# led_cube.net
KiCad netlist of a schematic drawn in EAGLE
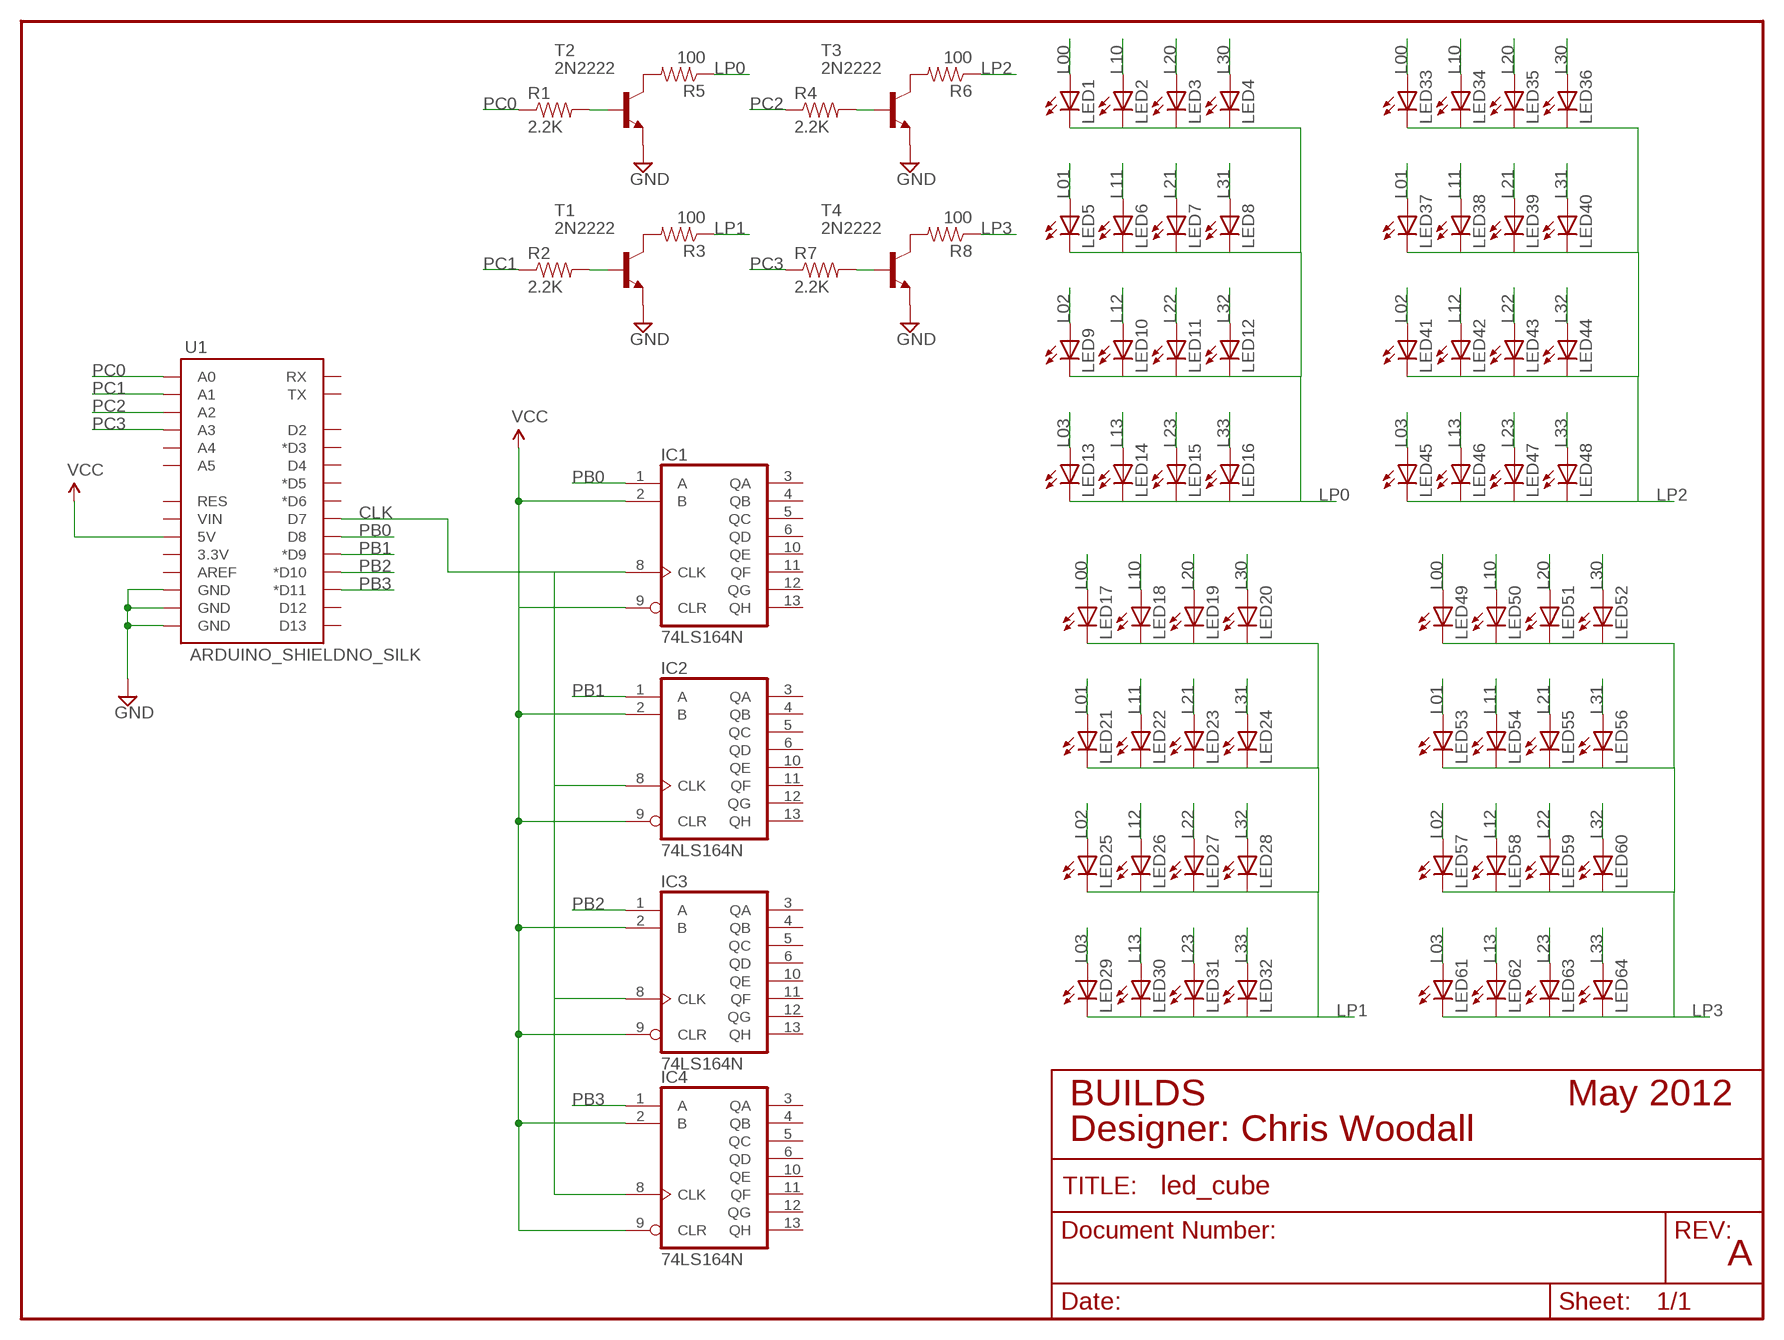
[diagram p0: schematic, sheet 1]

(export (version "E")
  (design (tool "Eeschema 10.0.6"))
  (components
    (comp (ref "IC1")
      (value "74LS164N")
      (footprint "eagle-import:DIL14")
      (libsource (lib "eagle-import") (part "74164NLS"))
    )
    (comp (ref "IC2")
      (value "74LS164N")
      (footprint "eagle-import:DIL14")
      (libsource (lib "eagle-import") (part "74164NLS"))
    )
    (comp (ref "IC3")
      (value "74LS164N")
      (footprint "eagle-import:DIL14")
      (libsource (lib "eagle-import") (part "74164NLS"))
    )
    (comp (ref "IC4")
      (value "74LS164N")
      (footprint "eagle-import:DIL14")
      (libsource (lib "eagle-import") (part "74164NLS"))
    )
    (comp (ref "LED1")
      (value "LED")
      (footprint "eagle-import:SMARTLED-TTW")
      (libsource (lib "eagle-import") (part "LED"))
    )
    (comp (ref "LED2")
      (value "LED")
      (footprint "eagle-import:SMARTLED-TTW")
      (libsource (lib "eagle-import") (part "LED"))
    )
    (comp (ref "LED3")
      (value "LED")
      (footprint "eagle-import:SMARTLED-TTW")
      (libsource (lib "eagle-import") (part "LED"))
    )
    (comp (ref "LED4")
      (value "LED")
      (footprint "eagle-import:SMARTLED-TTW")
      (libsource (lib "eagle-import") (part "LED"))
    )
    (comp (ref "LED5")
      (value "LED")
      (footprint "eagle-import:SMARTLED-TTW")
      (libsource (lib "eagle-import") (part "LED"))
    )
    (comp (ref "LED6")
      (value "LED")
      (footprint "eagle-import:SMARTLED-TTW")
      (libsource (lib "eagle-import") (part "LED"))
    )
    (comp (ref "LED7")
      (value "LED")
      (footprint "eagle-import:SMARTLED-TTW")
      (libsource (lib "eagle-import") (part "LED"))
    )
    (comp (ref "LED8")
      (value "LED")
      (footprint "eagle-import:SMARTLED-TTW")
      (libsource (lib "eagle-import") (part "LED"))
    )
    (comp (ref "LED9")
      (value "LED")
      (footprint "eagle-import:SMARTLED-TTW")
      (libsource (lib "eagle-import") (part "LED"))
    )
    (comp (ref "LED10")
      (value "LED")
      (footprint "eagle-import:SMARTLED-TTW")
      (libsource (lib "eagle-import") (part "LED"))
    )
    (comp (ref "LED11")
      (value "LED")
      (footprint "eagle-import:SMARTLED-TTW")
      (libsource (lib "eagle-import") (part "LED"))
    )
    (comp (ref "LED12")
      (value "LED")
      (footprint "eagle-import:SMARTLED-TTW")
      (libsource (lib "eagle-import") (part "LED"))
    )
    (comp (ref "LED13")
      (value "LED")
      (footprint "eagle-import:SMARTLED-TTW")
      (libsource (lib "eagle-import") (part "LED"))
    )
    (comp (ref "LED14")
      (value "LED")
      (footprint "eagle-import:SMARTLED-TTW")
      (libsource (lib "eagle-import") (part "LED"))
    )
    (comp (ref "LED15")
      (value "LED")
      (footprint "eagle-import:SMARTLED-TTW")
      (libsource (lib "eagle-import") (part "LED"))
    )
    (comp (ref "LED16")
      (value "LED")
      (footprint "eagle-import:SMARTLED-TTW")
      (libsource (lib "eagle-import") (part "LED"))
    )
    (comp (ref "LED17")
      (value "LED")
      (footprint "eagle-import:SMARTLED-TTW")
      (libsource (lib "eagle-import") (part "LED"))
    )
    (comp (ref "LED18")
      (value "LED")
      (footprint "eagle-import:SMARTLED-TTW")
      (libsource (lib "eagle-import") (part "LED"))
    )
    (comp (ref "LED19")
      (value "LED")
      (footprint "eagle-import:SMARTLED-TTW")
      (libsource (lib "eagle-import") (part "LED"))
    )
    (comp (ref "LED20")
      (value "LED")
      (footprint "eagle-import:SMARTLED-TTW")
      (libsource (lib "eagle-import") (part "LED"))
    )
    (comp (ref "LED21")
      (value "LED")
      (footprint "eagle-import:SMARTLED-TTW")
      (libsource (lib "eagle-import") (part "LED"))
    )
    (comp (ref "LED22")
      (value "LED")
      (footprint "eagle-import:SMARTLED-TTW")
      (libsource (lib "eagle-import") (part "LED"))
    )
    (comp (ref "LED23")
      (value "LED")
      (footprint "eagle-import:SMARTLED-TTW")
      (libsource (lib "eagle-import") (part "LED"))
    )
    (comp (ref "LED24")
      (value "LED")
      (footprint "eagle-import:SMARTLED-TTW")
      (libsource (lib "eagle-import") (part "LED"))
    )
    (comp (ref "LED25")
      (value "LED")
      (footprint "eagle-import:SMARTLED-TTW")
      (libsource (lib "eagle-import") (part "LED"))
    )
    (comp (ref "LED26")
      (value "LED")
      (footprint "eagle-import:SMARTLED-TTW")
      (libsource (lib "eagle-import") (part "LED"))
    )
    (comp (ref "LED27")
      (value "LED")
      (footprint "eagle-import:SMARTLED-TTW")
      (libsource (lib "eagle-import") (part "LED"))
    )
    (comp (ref "LED28")
      (value "LED")
      (footprint "eagle-import:SMARTLED-TTW")
      (libsource (lib "eagle-import") (part "LED"))
    )
    (comp (ref "LED29")
      (value "LED")
      (footprint "eagle-import:SMARTLED-TTW")
      (libsource (lib "eagle-import") (part "LED"))
    )
    (comp (ref "LED30")
      (value "LED")
      (footprint "eagle-import:SMARTLED-TTW")
      (libsource (lib "eagle-import") (part "LED"))
    )
    (comp (ref "LED31")
      (value "LED")
      (footprint "eagle-import:SMARTLED-TTW")
      (libsource (lib "eagle-import") (part "LED"))
    )
    (comp (ref "LED32")
      (value "LED")
      (footprint "eagle-import:SMARTLED-TTW")
      (libsource (lib "eagle-import") (part "LED"))
    )
    (comp (ref "LED33")
      (value "LED")
      (footprint "eagle-import:SMARTLED-TTW")
      (libsource (lib "eagle-import") (part "LED"))
    )
    (comp (ref "LED34")
      (value "LED")
      (footprint "eagle-import:SMARTLED-TTW")
      (libsource (lib "eagle-import") (part "LED"))
    )
    (comp (ref "LED35")
      (value "LED")
      (footprint "eagle-import:SMARTLED-TTW")
      (libsource (lib "eagle-import") (part "LED"))
    )
    (comp (ref "LED36")
      (value "LED")
      (footprint "eagle-import:SMARTLED-TTW")
      (libsource (lib "eagle-import") (part "LED"))
    )
    (comp (ref "LED37")
      (value "LED")
      (footprint "eagle-import:SMARTLED-TTW")
      (libsource (lib "eagle-import") (part "LED"))
    )
    (comp (ref "LED38")
      (value "LED")
      (footprint "eagle-import:SMARTLED-TTW")
      (libsource (lib "eagle-import") (part "LED"))
    )
    (comp (ref "LED39")
      (value "LED")
      (footprint "eagle-import:SMARTLED-TTW")
      (libsource (lib "eagle-import") (part "LED"))
    )
    (comp (ref "LED40")
      (value "LED")
      (footprint "eagle-import:SMARTLED-TTW")
      (libsource (lib "eagle-import") (part "LED"))
    )
    (comp (ref "LED41")
      (value "LED")
      (footprint "eagle-import:SMARTLED-TTW")
      (libsource (lib "eagle-import") (part "LED"))
    )
    (comp (ref "LED42")
      (value "LED")
      (footprint "eagle-import:SMARTLED-TTW")
      (libsource (lib "eagle-import") (part "LED"))
    )
    (comp (ref "LED43")
      (value "LED")
      (footprint "eagle-import:SMARTLED-TTW")
      (libsource (lib "eagle-import") (part "LED"))
    )
    (comp (ref "LED44")
      (value "LED")
      (footprint "eagle-import:SMARTLED-TTW")
      (libsource (lib "eagle-import") (part "LED"))
    )
    (comp (ref "LED45")
      (value "LED")
      (footprint "eagle-import:SMARTLED-TTW")
      (libsource (lib "eagle-import") (part "LED"))
    )
    (comp (ref "LED46")
      (value "LED")
      (footprint "eagle-import:SMARTLED-TTW")
      (libsource (lib "eagle-import") (part "LED"))
    )
    (comp (ref "LED47")
      (value "LED")
      (footprint "eagle-import:SMARTLED-TTW")
      (libsource (lib "eagle-import") (part "LED"))
    )
    (comp (ref "LED48")
      (value "LED")
      (footprint "eagle-import:SMARTLED-TTW")
      (libsource (lib "eagle-import") (part "LED"))
    )
    (comp (ref "LED49")
      (value "LED")
      (footprint "eagle-import:SMARTLED-TTW")
      (libsource (lib "eagle-import") (part "LED"))
    )
    (comp (ref "LED50")
      (value "LED")
      (footprint "eagle-import:SMARTLED-TTW")
      (libsource (lib "eagle-import") (part "LED"))
    )
    (comp (ref "LED51")
      (value "LED")
      (footprint "eagle-import:SMARTLED-TTW")
      (libsource (lib "eagle-import") (part "LED"))
    )
    (comp (ref "LED52")
      (value "LED")
      (footprint "eagle-import:SMARTLED-TTW")
      (libsource (lib "eagle-import") (part "LED"))
    )
    (comp (ref "LED53")
      (value "LED")
      (footprint "eagle-import:SMARTLED-TTW")
      (libsource (lib "eagle-import") (part "LED"))
    )
    (comp (ref "LED54")
      (value "LED")
      (footprint "eagle-import:SMARTLED-TTW")
      (libsource (lib "eagle-import") (part "LED"))
    )
    (comp (ref "LED55")
      (value "LED")
      (footprint "eagle-import:SMARTLED-TTW")
      (libsource (lib "eagle-import") (part "LED"))
    )
    (comp (ref "LED56")
      (value "LED")
      (footprint "eagle-import:SMARTLED-TTW")
      (libsource (lib "eagle-import") (part "LED"))
    )
    (comp (ref "LED57")
      (value "LED")
      (footprint "eagle-import:SMARTLED-TTW")
      (libsource (lib "eagle-import") (part "LED"))
    )
    (comp (ref "LED58")
      (value "LED")
      (footprint "eagle-import:SMARTLED-TTW")
      (libsource (lib "eagle-import") (part "LED"))
    )
    (comp (ref "LED59")
      (value "LED")
      (footprint "eagle-import:SMARTLED-TTW")
      (libsource (lib "eagle-import") (part "LED"))
    )
    (comp (ref "LED60")
      (value "LED")
      (footprint "eagle-import:SMARTLED-TTW")
      (libsource (lib "eagle-import") (part "LED"))
    )
    (comp (ref "LED61")
      (value "LED")
      (footprint "eagle-import:SMARTLED-TTW")
      (libsource (lib "eagle-import") (part "LED"))
    )
    (comp (ref "LED62")
      (value "LED")
      (footprint "eagle-import:SMARTLED-TTW")
      (libsource (lib "eagle-import") (part "LED"))
    )
    (comp (ref "LED63")
      (value "LED")
      (footprint "eagle-import:SMARTLED-TTW")
      (libsource (lib "eagle-import") (part "LED"))
    )
    (comp (ref "LED64")
      (value "LED")
      (footprint "eagle-import:SMARTLED-TTW")
      (libsource (lib "eagle-import") (part "LED"))
    )
    (comp (ref "R1")
      (value "2.2K")
      (footprint "eagle-import:0603-RES")
      (libsource (lib "eagle-import") (part "RESISTOR0603-RES"))
    )
    (comp (ref "R2")
      (value "2.2K")
      (footprint "eagle-import:0603-RES")
      (libsource (lib "eagle-import") (part "RESISTOR0603-RES"))
    )
    (comp (ref "R3")
      (value "100")
      (footprint "eagle-import:0603-RES")
      (libsource (lib "eagle-import") (part "RESISTOR0603-RES"))
    )
    (comp (ref "R4")
      (value "2.2K")
      (footprint "eagle-import:0603-RES")
      (libsource (lib "eagle-import") (part "RESISTOR0603-RES"))
    )
    (comp (ref "R5")
      (value "100")
      (footprint "eagle-import:0603-RES")
      (libsource (lib "eagle-import") (part "RESISTOR0603-RES"))
    )
    (comp (ref "R6")
      (value "100")
      (footprint "eagle-import:0603-RES")
      (libsource (lib "eagle-import") (part "RESISTOR0603-RES"))
    )
    (comp (ref "R7")
      (value "2.2K")
      (footprint "eagle-import:0603-RES")
      (libsource (lib "eagle-import") (part "RESISTOR0603-RES"))
    )
    (comp (ref "R8")
      (value "100")
      (footprint "eagle-import:0603-RES")
      (libsource (lib "eagle-import") (part "RESISTOR0603-RES"))
    )
    (comp (ref "T1")
      (value "2N2222")
      (footprint "eagle-import:TO92-EBC-OVAL")
      (libsource (lib "eagle-import") (part "2N2222"))
    )
    (comp (ref "T2")
      (value "2N2222")
      (footprint "eagle-import:TO92-EBC-OVAL")
      (libsource (lib "eagle-import") (part "2N2222"))
    )
    (comp (ref "T3")
      (value "2N2222")
      (footprint "eagle-import:TO92-EBC-OVAL")
      (libsource (lib "eagle-import") (part "2N2222"))
    )
    (comp (ref "T4")
      (value "2N2222")
      (footprint "eagle-import:TO92-EBC-OVAL")
      (libsource (lib "eagle-import") (part "2N2222"))
    )
    (comp (ref "U1")
      (value "ARDUINO_SHIELDNO_SILK")
      (footprint "eagle-import:DUEMILANOVE_VIAS")
      (libsource (lib "eagle-import") (part "ARDUINO_SHIELDNO_SILK"))
    )
  )
  (nets
    (net (code "1") (name "/CLK") (class "Default")
      (node (ref "IC1") (pin "8") (pinfunction "CLK_8") (pintype "input"))
      (node (ref "IC2") (pin "8") (pinfunction "CLK_8") (pintype "input"))
      (node (ref "IC3") (pin "8") (pinfunction "CLK_8") (pintype "input"))
      (node (ref "IC4") (pin "8") (pinfunction "CLK_8") (pintype "input"))
      (node (ref "U1") (pin "D7") (pinfunction "D7_D7") (pintype "bidirectional"))
    )
    (net (code "2") (name "/L00") (class "Default")
      (node (ref "LED1") (pin "A@1") (pinfunction "A_A@1") (pintype "passive"))
      (node (ref "LED17") (pin "A@1") (pinfunction "A_A@1") (pintype "passive"))
      (node (ref "LED33") (pin "A@1") (pinfunction "A_A@1") (pintype "passive"))
      (node (ref "LED49") (pin "A@1") (pinfunction "A_A@1") (pintype "passive"))
    )
    (net (code "3") (name "/L01") (class "Default")
      (node (ref "LED21") (pin "A@1") (pinfunction "A_A@1") (pintype "passive"))
      (node (ref "LED37") (pin "A@1") (pinfunction "A_A@1") (pintype "passive"))
      (node (ref "LED5") (pin "A@1") (pinfunction "A_A@1") (pintype "passive"))
      (node (ref "LED53") (pin "A@1") (pinfunction "A_A@1") (pintype "passive"))
    )
    (net (code "4") (name "/L02") (class "Default")
      (node (ref "LED25") (pin "A@1") (pinfunction "A_A@1") (pintype "passive"))
      (node (ref "LED41") (pin "A@1") (pinfunction "A_A@1") (pintype "passive"))
      (node (ref "LED57") (pin "A@1") (pinfunction "A_A@1") (pintype "passive"))
      (node (ref "LED9") (pin "A@1") (pinfunction "A_A@1") (pintype "passive"))
    )
    (net (code "5") (name "/L03") (class "Default")
      (node (ref "LED13") (pin "A@1") (pinfunction "A_A@1") (pintype "passive"))
      (node (ref "LED29") (pin "A@1") (pinfunction "A_A@1") (pintype "passive"))
      (node (ref "LED45") (pin "A@1") (pinfunction "A_A@1") (pintype "passive"))
      (node (ref "LED61") (pin "A@1") (pinfunction "A_A@1") (pintype "passive"))
    )
    (net (code "6") (name "/L10") (class "Default")
      (node (ref "LED18") (pin "A@1") (pinfunction "A_A@1") (pintype "passive"))
      (node (ref "LED2") (pin "A@1") (pinfunction "A_A@1") (pintype "passive"))
      (node (ref "LED34") (pin "A@1") (pinfunction "A_A@1") (pintype "passive"))
      (node (ref "LED50") (pin "A@1") (pinfunction "A_A@1") (pintype "passive"))
    )
    (net (code "7") (name "/L11") (class "Default")
      (node (ref "LED22") (pin "A@1") (pinfunction "A_A@1") (pintype "passive"))
      (node (ref "LED38") (pin "A@1") (pinfunction "A_A@1") (pintype "passive"))
      (node (ref "LED54") (pin "A@1") (pinfunction "A_A@1") (pintype "passive"))
      (node (ref "LED6") (pin "A@1") (pinfunction "A_A@1") (pintype "passive"))
    )
    (net (code "8") (name "/L12") (class "Default")
      (node (ref "LED10") (pin "A@1") (pinfunction "A_A@1") (pintype "passive"))
      (node (ref "LED26") (pin "A@1") (pinfunction "A_A@1") (pintype "passive"))
      (node (ref "LED42") (pin "A@1") (pinfunction "A_A@1") (pintype "passive"))
      (node (ref "LED58") (pin "A@1") (pinfunction "A_A@1") (pintype "passive"))
    )
    (net (code "9") (name "/L13") (class "Default")
      (node (ref "LED14") (pin "A@1") (pinfunction "A_A@1") (pintype "passive"))
      (node (ref "LED30") (pin "A@1") (pinfunction "A_A@1") (pintype "passive"))
      (node (ref "LED46") (pin "A@1") (pinfunction "A_A@1") (pintype "passive"))
      (node (ref "LED62") (pin "A@1") (pinfunction "A_A@1") (pintype "passive"))
    )
    (net (code "10") (name "/L20") (class "Default")
      (node (ref "LED19") (pin "A@1") (pinfunction "A_A@1") (pintype "passive"))
      (node (ref "LED3") (pin "A@1") (pinfunction "A_A@1") (pintype "passive"))
      (node (ref "LED35") (pin "A@1") (pinfunction "A_A@1") (pintype "passive"))
      (node (ref "LED51") (pin "A@1") (pinfunction "A_A@1") (pintype "passive"))
    )
    (net (code "11") (name "/L21") (class "Default")
      (node (ref "LED23") (pin "A@1") (pinfunction "A_A@1") (pintype "passive"))
      (node (ref "LED39") (pin "A@1") (pinfunction "A_A@1") (pintype "passive"))
      (node (ref "LED55") (pin "A@1") (pinfunction "A_A@1") (pintype "passive"))
      (node (ref "LED7") (pin "A@1") (pinfunction "A_A@1") (pintype "passive"))
    )
    (net (code "12") (name "/L22") (class "Default")
      (node (ref "LED11") (pin "A@1") (pinfunction "A_A@1") (pintype "passive"))
      (node (ref "LED27") (pin "A@1") (pinfunction "A_A@1") (pintype "passive"))
      (node (ref "LED43") (pin "A@1") (pinfunction "A_A@1") (pintype "passive"))
      (node (ref "LED59") (pin "A@1") (pinfunction "A_A@1") (pintype "passive"))
    )
    (net (code "13") (name "/L23") (class "Default")
      (node (ref "LED15") (pin "A@1") (pinfunction "A_A@1") (pintype "passive"))
      (node (ref "LED31") (pin "A@1") (pinfunction "A_A@1") (pintype "passive"))
      (node (ref "LED47") (pin "A@1") (pinfunction "A_A@1") (pintype "passive"))
      (node (ref "LED63") (pin "A@1") (pinfunction "A_A@1") (pintype "passive"))
    )
    (net (code "14") (name "/L30") (class "Default")
      (node (ref "LED20") (pin "A@1") (pinfunction "A_A@1") (pintype "passive"))
      (node (ref "LED36") (pin "A@1") (pinfunction "A_A@1") (pintype "passive"))
      (node (ref "LED4") (pin "A@1") (pinfunction "A_A@1") (pintype "passive"))
      (node (ref "LED52") (pin "A@1") (pinfunction "A_A@1") (pintype "passive"))
    )
    (net (code "15") (name "/L31") (class "Default")
      (node (ref "LED24") (pin "A@1") (pinfunction "A_A@1") (pintype "passive"))
      (node (ref "LED40") (pin "A@1") (pinfunction "A_A@1") (pintype "passive"))
      (node (ref "LED56") (pin "A@1") (pinfunction "A_A@1") (pintype "passive"))
      (node (ref "LED8") (pin "A@1") (pinfunction "A_A@1") (pintype "passive"))
    )
    (net (code "16") (name "/L32") (class "Default")
      (node (ref "LED12") (pin "A@1") (pinfunction "A_A@1") (pintype "passive"))
      (node (ref "LED28") (pin "A@1") (pinfunction "A_A@1") (pintype "passive"))
      (node (ref "LED44") (pin "A@1") (pinfunction "A_A@1") (pintype "passive"))
      (node (ref "LED60") (pin "A@1") (pinfunction "A_A@1") (pintype "passive"))
    )
    (net (code "17") (name "/L33") (class "Default")
      (node (ref "LED16") (pin "A@1") (pinfunction "A_A@1") (pintype "passive"))
      (node (ref "LED32") (pin "A@1") (pinfunction "A_A@1") (pintype "passive"))
      (node (ref "LED48") (pin "A@1") (pinfunction "A_A@1") (pintype "passive"))
      (node (ref "LED64") (pin "A@1") (pinfunction "A_A@1") (pintype "passive"))
    )
    (net (code "18") (name "/LP0") (class "Default")
      (node (ref "LED1") (pin "C@1") (pinfunction "C_C@1") (pintype "passive"))
      (node (ref "LED10") (pin "C@1") (pinfunction "C_C@1") (pintype "passive"))
      (node (ref "LED11") (pin "C@1") (pinfunction "C_C@1") (pintype "passive"))
      (node (ref "LED12") (pin "C@1") (pinfunction "C_C@1") (pintype "passive"))
      (node (ref "LED13") (pin "C@1") (pinfunction "C_C@1") (pintype "passive"))
      (node (ref "LED14") (pin "C@1") (pinfunction "C_C@1") (pintype "passive"))
      (node (ref "LED15") (pin "C@1") (pinfunction "C_C@1") (pintype "passive"))
      (node (ref "LED16") (pin "C@1") (pinfunction "C_C@1") (pintype "passive"))
      (node (ref "LED2") (pin "C@1") (pinfunction "C_C@1") (pintype "passive"))
      (node (ref "LED3") (pin "C@1") (pinfunction "C_C@1") (pintype "passive"))
      (node (ref "LED4") (pin "C@1") (pinfunction "C_C@1") (pintype "passive"))
      (node (ref "LED5") (pin "C@1") (pinfunction "C_C@1") (pintype "passive"))
      (node (ref "LED6") (pin "C@1") (pinfunction "C_C@1") (pintype "passive"))
      (node (ref "LED7") (pin "C@1") (pinfunction "C_C@1") (pintype "passive"))
      (node (ref "LED8") (pin "C@1") (pinfunction "C_C@1") (pintype "passive"))
      (node (ref "LED9") (pin "C@1") (pinfunction "C_C@1") (pintype "passive"))
      (node (ref "R5") (pin "1") (pinfunction "1_1") (pintype "passive"))
    )
    (net (code "19") (name "/LP1") (class "Default")
      (node (ref "LED17") (pin "C@1") (pinfunction "C_C@1") (pintype "passive"))
      (node (ref "LED18") (pin "C@1") (pinfunction "C_C@1") (pintype "passive"))
      (node (ref "LED19") (pin "C@1") (pinfunction "C_C@1") (pintype "passive"))
      (node (ref "LED20") (pin "C@1") (pinfunction "C_C@1") (pintype "passive"))
      (node (ref "LED21") (pin "C@1") (pinfunction "C_C@1") (pintype "passive"))
      (node (ref "LED22") (pin "C@1") (pinfunction "C_C@1") (pintype "passive"))
      (node (ref "LED23") (pin "C@1") (pinfunction "C_C@1") (pintype "passive"))
      (node (ref "LED24") (pin "C@1") (pinfunction "C_C@1") (pintype "passive"))
      (node (ref "LED25") (pin "C@1") (pinfunction "C_C@1") (pintype "passive"))
      (node (ref "LED26") (pin "C@1") (pinfunction "C_C@1") (pintype "passive"))
      (node (ref "LED27") (pin "C@1") (pinfunction "C_C@1") (pintype "passive"))
      (node (ref "LED28") (pin "C@1") (pinfunction "C_C@1") (pintype "passive"))
      (node (ref "LED29") (pin "C@1") (pinfunction "C_C@1") (pintype "passive"))
      (node (ref "LED30") (pin "C@1") (pinfunction "C_C@1") (pintype "passive"))
      (node (ref "LED31") (pin "C@1") (pinfunction "C_C@1") (pintype "passive"))
      (node (ref "LED32") (pin "C@1") (pinfunction "C_C@1") (pintype "passive"))
      (node (ref "R3") (pin "1") (pinfunction "1_1") (pintype "passive"))
    )
    (net (code "20") (name "/LP2") (class "Default")
      (node (ref "LED33") (pin "C@1") (pinfunction "C_C@1") (pintype "passive"))
      (node (ref "LED34") (pin "C@1") (pinfunction "C_C@1") (pintype "passive"))
      (node (ref "LED35") (pin "C@1") (pinfunction "C_C@1") (pintype "passive"))
      (node (ref "LED36") (pin "C@1") (pinfunction "C_C@1") (pintype "passive"))
      (node (ref "LED37") (pin "C@1") (pinfunction "C_C@1") (pintype "passive"))
      (node (ref "LED38") (pin "C@1") (pinfunction "C_C@1") (pintype "passive"))
      (node (ref "LED39") (pin "C@1") (pinfunction "C_C@1") (pintype "passive"))
      (node (ref "LED40") (pin "C@1") (pinfunction "C_C@1") (pintype "passive"))
      (node (ref "LED41") (pin "C@1") (pinfunction "C_C@1") (pintype "passive"))
      (node (ref "LED42") (pin "C@1") (pinfunction "C_C@1") (pintype "passive"))
      (node (ref "LED43") (pin "C@1") (pinfunction "C_C@1") (pintype "passive"))
      (node (ref "LED44") (pin "C@1") (pinfunction "C_C@1") (pintype "passive"))
      (node (ref "LED45") (pin "C@1") (pinfunction "C_C@1") (pintype "passive"))
      (node (ref "LED46") (pin "C@1") (pinfunction "C_C@1") (pintype "passive"))
      (node (ref "LED47") (pin "C@1") (pinfunction "C_C@1") (pintype "passive"))
      (node (ref "LED48") (pin "C@1") (pinfunction "C_C@1") (pintype "passive"))
      (node (ref "R6") (pin "1") (pinfunction "1_1") (pintype "passive"))
    )
    (net (code "21") (name "/LP3") (class "Default")
      (node (ref "LED49") (pin "C@1") (pinfunction "C_C@1") (pintype "passive"))
      (node (ref "LED50") (pin "C@1") (pinfunction "C_C@1") (pintype "passive"))
      (node (ref "LED51") (pin "C@1") (pinfunction "C_C@1") (pintype "passive"))
      (node (ref "LED52") (pin "C@1") (pinfunction "C_C@1") (pintype "passive"))
      (node (ref "LED53") (pin "C@1") (pinfunction "C_C@1") (pintype "passive"))
      (node (ref "LED54") (pin "C@1") (pinfunction "C_C@1") (pintype "passive"))
      (node (ref "LED55") (pin "C@1") (pinfunction "C_C@1") (pintype "passive"))
      (node (ref "LED56") (pin "C@1") (pinfunction "C_C@1") (pintype "passive"))
      (node (ref "LED57") (pin "C@1") (pinfunction "C_C@1") (pintype "passive"))
      (node (ref "LED58") (pin "C@1") (pinfunction "C_C@1") (pintype "passive"))
      (node (ref "LED59") (pin "C@1") (pinfunction "C_C@1") (pintype "passive"))
      (node (ref "LED60") (pin "C@1") (pinfunction "C_C@1") (pintype "passive"))
      (node (ref "LED61") (pin "C@1") (pinfunction "C_C@1") (pintype "passive"))
      (node (ref "LED62") (pin "C@1") (pinfunction "C_C@1") (pintype "passive"))
      (node (ref "LED63") (pin "C@1") (pinfunction "C_C@1") (pintype "passive"))
      (node (ref "LED64") (pin "C@1") (pinfunction "C_C@1") (pintype "passive"))
      (node (ref "R8") (pin "1") (pinfunction "1_1") (pintype "passive"))
    )
    (net (code "22") (name "/PB0") (class "Default")
      (node (ref "IC1") (pin "1") (pinfunction "A_1") (pintype "input"))
      (node (ref "U1") (pin "D8") (pinfunction "D8_D8") (pintype "bidirectional"))
    )
    (net (code "23") (name "/PB1") (class "Default")
      (node (ref "IC2") (pin "1") (pinfunction "A_1") (pintype "input"))
      (node (ref "U1") (pin "D9") (pinfunction "*D9_D9") (pintype "bidirectional"))
    )
    (net (code "24") (name "/PB2") (class "Default")
      (node (ref "IC3") (pin "1") (pinfunction "A_1") (pintype "input"))
      (node (ref "U1") (pin "D10") (pinfunction "*D10_D10") (pintype "bidirectional"))
    )
    (net (code "25") (name "/PB3") (class "Default")
      (node (ref "IC4") (pin "1") (pinfunction "A_1") (pintype "input"))
      (node (ref "U1") (pin "D11") (pinfunction "*D11_D11") (pintype "bidirectional"))
    )
    (net (code "26") (name "/PC0") (class "Default")
      (node (ref "R1") (pin "1") (pinfunction "1_1") (pintype "passive"))
      (node (ref "U1") (pin "A0") (pinfunction "A0_A0") (pintype "bidirectional"))
    )
    (net (code "27") (name "/PC1") (class "Default")
      (node (ref "R2") (pin "1") (pinfunction "1_1") (pintype "passive"))
      (node (ref "U1") (pin "A1") (pinfunction "A1_A1") (pintype "bidirectional"))
    )
    (net (code "28") (name "/PC2") (class "Default")
      (node (ref "R4") (pin "1") (pinfunction "1_1") (pintype "passive"))
      (node (ref "U1") (pin "A2") (pinfunction "A2_A2") (pintype "bidirectional"))
    )
    (net (code "29") (name "/PC3") (class "Default")
      (node (ref "R7") (pin "1") (pinfunction "1_1") (pintype "passive"))
      (node (ref "U1") (pin "A3") (pinfunction "A3_A3") (pintype "bidirectional"))
    )
    (net (code "30") (name "GND") (class "Default")
      (node (ref "T1") (pin "E") (pinfunction "E_E") (pintype "passive"))
      (node (ref "T2") (pin "E") (pinfunction "E_E") (pintype "passive"))
      (node (ref "T3") (pin "E") (pinfunction "E_E") (pintype "passive"))
      (node (ref "T4") (pin "E") (pinfunction "E_E") (pintype "passive"))
      (node (ref "U1") (pin "GND@0") (pinfunction "GND_GND@0") (pintype "bidirectional"))
      (node (ref "U1") (pin "GND@1") (pinfunction "GND_GND@1") (pintype "bidirectional"))
      (node (ref "U1") (pin "GND@2") (pinfunction "GND_GND@2") (pintype "bidirectional"))
    )
    (net (code "31") (name "Net-(R1-Pad2)") (class "Default")
      (node (ref "R1") (pin "2") (pinfunction "2_2") (pintype "passive"))
      (node (ref "T2") (pin "B") (pinfunction "B_B") (pintype "passive"))
    )
    (net (code "32") (name "Net-(R2-Pad2)") (class "Default")
      (node (ref "R2") (pin "2") (pinfunction "2_2") (pintype "passive"))
      (node (ref "T1") (pin "B") (pinfunction "B_B") (pintype "passive"))
    )
    (net (code "33") (name "Net-(R3-Pad2)") (class "Default")
      (node (ref "R3") (pin "2") (pinfunction "2_2") (pintype "passive"))
      (node (ref "T1") (pin "C") (pinfunction "C_C") (pintype "passive"))
    )
    (net (code "34") (name "Net-(R4-Pad2)") (class "Default")
      (node (ref "R4") (pin "2") (pinfunction "2_2") (pintype "passive"))
      (node (ref "T3") (pin "B") (pinfunction "B_B") (pintype "passive"))
    )
    (net (code "35") (name "Net-(R5-Pad2)") (class "Default")
      (node (ref "R5") (pin "2") (pinfunction "2_2") (pintype "passive"))
      (node (ref "T2") (pin "C") (pinfunction "C_C") (pintype "passive"))
    )
    (net (code "36") (name "Net-(R6-Pad2)") (class "Default")
      (node (ref "R6") (pin "2") (pinfunction "2_2") (pintype "passive"))
      (node (ref "T3") (pin "C") (pinfunction "C_C") (pintype "passive"))
    )
    (net (code "37") (name "Net-(R7-Pad2)") (class "Default")
      (node (ref "R7") (pin "2") (pinfunction "2_2") (pintype "passive"))
      (node (ref "T4") (pin "B") (pinfunction "B_B") (pintype "passive"))
    )
    (net (code "38") (name "Net-(R8-Pad2)") (class "Default")
      (node (ref "R8") (pin "2") (pinfunction "2_2") (pintype "passive"))
      (node (ref "T4") (pin "C") (pinfunction "C_C") (pintype "passive"))
    )
    (net (code "39") (name "VCC") (class "Default")
      (node (ref "IC1") (pin "2") (pinfunction "B_2") (pintype "input"))
      (node (ref "IC1") (pin "9") (pinfunction "CLR_9") (pintype "input"))
      (node (ref "IC2") (pin "2") (pinfunction "B_2") (pintype "input"))
      (node (ref "IC2") (pin "9") (pinfunction "CLR_9") (pintype "input"))
      (node (ref "IC3") (pin "2") (pinfunction "B_2") (pintype "input"))
      (node (ref "IC3") (pin "9") (pinfunction "CLR_9") (pintype "input"))
      (node (ref "IC4") (pin "2") (pinfunction "B_2") (pintype "input"))
      (node (ref "IC4") (pin "9") (pinfunction "CLR_9") (pintype "input"))
      (node (ref "U1") (pin "5V") (pinfunction "5V_5V") (pintype "bidirectional"))
    )
    (net (code "40") (name "unconnected-(IC1A-QA-Pad3)") (class "Default")
      (node (ref "IC1") (pin "3") (pinfunction "QA_3") (pintype "output"))
    )
    (net (code "41") (name "unconnected-(IC1A-QB-Pad4)") (class "Default")
      (node (ref "IC1") (pin "4") (pinfunction "QB_4") (pintype "output"))
    )
    (net (code "42") (name "unconnected-(IC1A-QC-Pad5)") (class "Default")
      (node (ref "IC1") (pin "5") (pinfunction "QC_5") (pintype "output"))
    )
    (net (code "43") (name "unconnected-(IC1A-QD-Pad6)") (class "Default")
      (node (ref "IC1") (pin "6") (pinfunction "QD_6") (pintype "output"))
    )
    (net (code "44") (name "unconnected-(IC1A-QE-Pad10)") (class "Default")
      (node (ref "IC1") (pin "10") (pinfunction "QE_10") (pintype "output"))
    )
    (net (code "45") (name "unconnected-(IC1A-QF-Pad11)") (class "Default")
      (node (ref "IC1") (pin "11") (pinfunction "QF_11") (pintype "output"))
    )
    (net (code "46") (name "unconnected-(IC1A-QG-Pad12)") (class "Default")
      (node (ref "IC1") (pin "12") (pinfunction "QG_12") (pintype "output"))
    )
    (net (code "47") (name "unconnected-(IC1A-QH-Pad13)") (class "Default")
      (node (ref "IC1") (pin "13") (pinfunction "QH_13") (pintype "output"))
    )
    (net (code "48") (name "unconnected-(IC2A-QA-Pad3)") (class "Default")
      (node (ref "IC2") (pin "3") (pinfunction "QA_3") (pintype "output"))
    )
    (net (code "49") (name "unconnected-(IC2A-QB-Pad4)") (class "Default")
      (node (ref "IC2") (pin "4") (pinfunction "QB_4") (pintype "output"))
    )
    (net (code "50") (name "unconnected-(IC2A-QC-Pad5)") (class "Default")
      (node (ref "IC2") (pin "5") (pinfunction "QC_5") (pintype "output"))
    )
    (net (code "51") (name "unconnected-(IC2A-QD-Pad6)") (class "Default")
      (node (ref "IC2") (pin "6") (pinfunction "QD_6") (pintype "output"))
    )
    (net (code "52") (name "unconnected-(IC2A-QE-Pad10)") (class "Default")
      (node (ref "IC2") (pin "10") (pinfunction "QE_10") (pintype "output"))
    )
    (net (code "53") (name "unconnected-(IC2A-QF-Pad11)") (class "Default")
      (node (ref "IC2") (pin "11") (pinfunction "QF_11") (pintype "output"))
    )
    (net (code "54") (name "unconnected-(IC2A-QG-Pad12)") (class "Default")
      (node (ref "IC2") (pin "12") (pinfunction "QG_12") (pintype "output"))
    )
    (net (code "55") (name "unconnected-(IC2A-QH-Pad13)") (class "Default")
      (node (ref "IC2") (pin "13") (pinfunction "QH_13") (pintype "output"))
    )
    (net (code "56") (name "unconnected-(IC3A-QA-Pad3)") (class "Default")
      (node (ref "IC3") (pin "3") (pinfunction "QA_3") (pintype "output"))
    )
    (net (code "57") (name "unconnected-(IC3A-QB-Pad4)") (class "Default")
      (node (ref "IC3") (pin "4") (pinfunction "QB_4") (pintype "output"))
    )
    (net (code "58") (name "unconnected-(IC3A-QC-Pad5)") (class "Default")
      (node (ref "IC3") (pin "5") (pinfunction "QC_5") (pintype "output"))
    )
    (net (code "59") (name "unconnected-(IC3A-QD-Pad6)") (class "Default")
      (node (ref "IC3") (pin "6") (pinfunction "QD_6") (pintype "output"))
    )
    (net (code "60") (name "unconnected-(IC3A-QE-Pad10)") (class "Default")
      (node (ref "IC3") (pin "10") (pinfunction "QE_10") (pintype "output"))
    )
    (net (code "61") (name "unconnected-(IC3A-QF-Pad11)") (class "Default")
      (node (ref "IC3") (pin "11") (pinfunction "QF_11") (pintype "output"))
    )
    (net (code "62") (name "unconnected-(IC3A-QG-Pad12)") (class "Default")
      (node (ref "IC3") (pin "12") (pinfunction "QG_12") (pintype "output"))
    )
    (net (code "63") (name "unconnected-(IC3A-QH-Pad13)") (class "Default")
      (node (ref "IC3") (pin "13") (pinfunction "QH_13") (pintype "output"))
    )
    (net (code "64") (name "unconnected-(IC4A-QA-Pad3)") (class "Default")
      (node (ref "IC4") (pin "3") (pinfunction "QA_3") (pintype "output"))
    )
    (net (code "65") (name "unconnected-(IC4A-QB-Pad4)") (class "Default")
      (node (ref "IC4") (pin "4") (pinfunction "QB_4") (pintype "output"))
    )
    (net (code "66") (name "unconnected-(IC4A-QC-Pad5)") (class "Default")
      (node (ref "IC4") (pin "5") (pinfunction "QC_5") (pintype "output"))
    )
    (net (code "67") (name "unconnected-(IC4A-QD-Pad6)") (class "Default")
      (node (ref "IC4") (pin "6") (pinfunction "QD_6") (pintype "output"))
    )
    (net (code "68") (name "unconnected-(IC4A-QE-Pad10)") (class "Default")
      (node (ref "IC4") (pin "10") (pinfunction "QE_10") (pintype "output"))
    )
    (net (code "69") (name "unconnected-(IC4A-QF-Pad11)") (class "Default")
      (node (ref "IC4") (pin "11") (pinfunction "QF_11") (pintype "output"))
    )
    (net (code "70") (name "unconnected-(IC4A-QG-Pad12)") (class "Default")
      (node (ref "IC4") (pin "12") (pinfunction "QG_12") (pintype "output"))
    )
    (net (code "71") (name "unconnected-(IC4A-QH-Pad13)") (class "Default")
      (node (ref "IC4") (pin "13") (pinfunction "QH_13") (pintype "output"))
    )
    (net (code "72") (name "unconnected-(U1-*D3-PadD3)") (class "Default")
      (node (ref "U1") (pin "D3") (pinfunction "*D3_D3") (pintype "bidirectional"))
    )
    (net (code "73") (name "unconnected-(U1-*D5-PadD5)") (class "Default")
      (node (ref "U1") (pin "D5") (pinfunction "*D5_D5") (pintype "bidirectional"))
    )
    (net (code "74") (name "unconnected-(U1-*D6-PadD6)") (class "Default")
      (node (ref "U1") (pin "D6") (pinfunction "*D6_D6") (pintype "bidirectional"))
    )
    (net (code "75") (name "unconnected-(U1-Pad3.3V)") (class "Default")
      (node (ref "U1") (pin "3.3V") (pinfunction "3.3V_3.3V") (pintype "bidirectional"))
    )
    (net (code "76") (name "unconnected-(U1-PadA4)") (class "Default")
      (node (ref "U1") (pin "A4") (pinfunction "A4_A4") (pintype "bidirectional"))
    )
    (net (code "77") (name "unconnected-(U1-PadA5)") (class "Default")
      (node (ref "U1") (pin "A5") (pinfunction "A5_A5") (pintype "bidirectional"))
    )
    (net (code "78") (name "unconnected-(U1-PadAREF)") (class "Default")
      (node (ref "U1") (pin "AREF") (pinfunction "AREF_AREF") (pintype "bidirectional"))
    )
    (net (code "79") (name "unconnected-(U1-PadD2)") (class "Default")
      (node (ref "U1") (pin "D2") (pinfunction "D2_D2") (pintype "bidirectional"))
    )
    (net (code "80") (name "unconnected-(U1-PadD4)") (class "Default")
      (node (ref "U1") (pin "D4") (pinfunction "D4_D4") (pintype "bidirectional"))
    )
    (net (code "81") (name "unconnected-(U1-PadD12)") (class "Default")
      (node (ref "U1") (pin "D12") (pinfunction "D12_D12") (pintype "bidirectional"))
    )
    (net (code "82") (name "unconnected-(U1-PadD13)") (class "Default")
      (node (ref "U1") (pin "D13") (pinfunction "D13_D13") (pintype "bidirectional"))
    )
    (net (code "83") (name "unconnected-(U1-PadRES)") (class "Default")
      (node (ref "U1") (pin "RES") (pinfunction "RES_RES") (pintype "bidirectional"))
    )
    (net (code "84") (name "unconnected-(U1-PadRX)") (class "Default")
      (node (ref "U1") (pin "RX") (pinfunction "RX_RX") (pintype "bidirectional"))
    )
    (net (code "85") (name "unconnected-(U1-PadTX)") (class "Default")
      (node (ref "U1") (pin "TX") (pinfunction "TX_TX") (pintype "bidirectional"))
    )
    (net (code "86") (name "unconnected-(U1-PadVIN)") (class "Default")
      (node (ref "U1") (pin "VIN") (pinfunction "VIN_VIN") (pintype "bidirectional"))
    )
  )
)
